# Dual_LPF_V1_2_Bottom.net
KiCad netlist of a schematic drawn in EAGLE
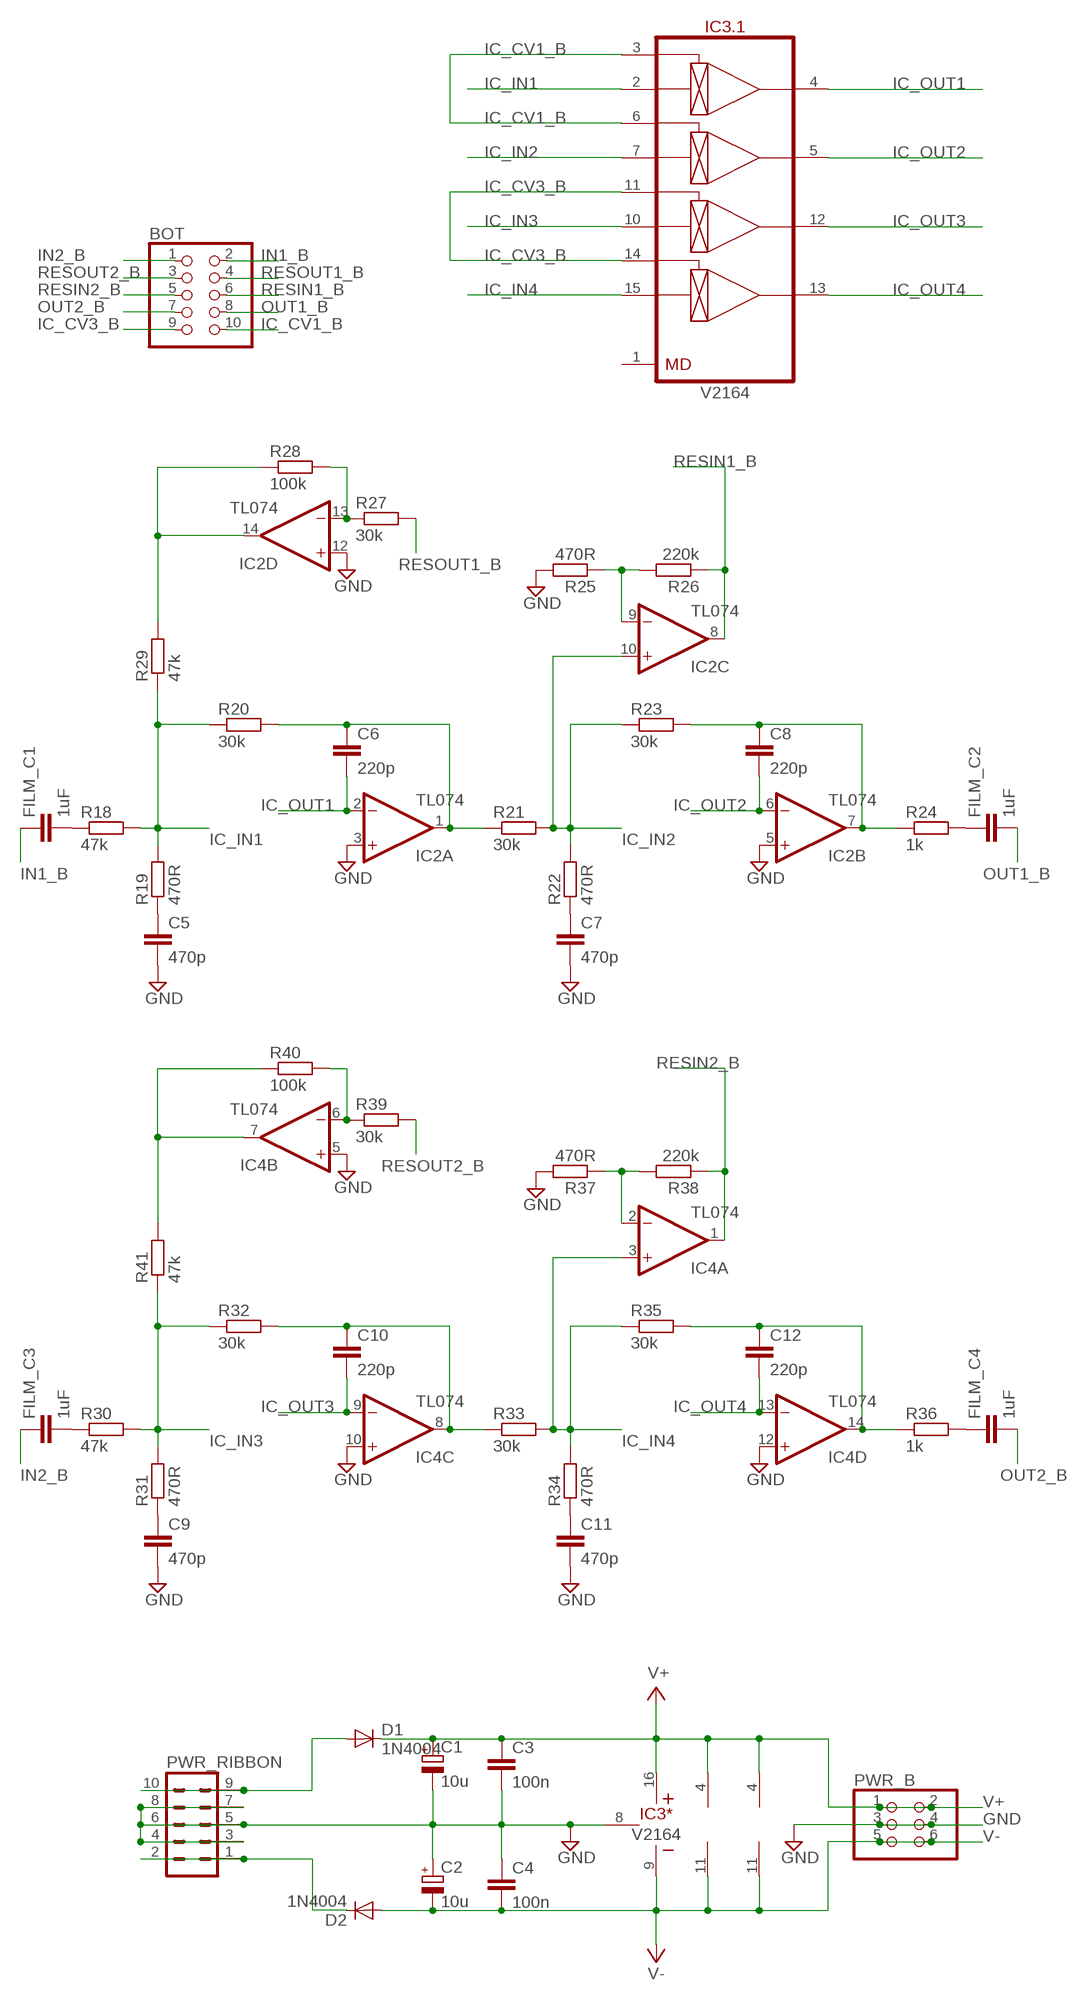
[diagram p0: schematic, sheet 1]

(export (version "E")
  (design (tool "Eeschema 10.0.6"))
  (components
    (comp (ref "BOT")
      (value "PINHD-2X5")
      (footprint "eagle-import:2X05")
      (libsource (lib "eagle-import") (part "PINHD-2X5"))
    )
    (comp (ref "C1")
      (value "10u")
      (footprint "eagle-import:E5-10,5")
      (libsource (lib "eagle-import") (part "CPOL-EUE5-10.5"))
    )
    (comp (ref "C2")
      (value "10u")
      (footprint "eagle-import:E5-10,5")
      (libsource (lib "eagle-import") (part "CPOL-EUE5-10.5"))
    )
    (comp (ref "C3")
      (value "100n")
      (footprint "eagle-import:C050-024X044")
      (libsource (lib "eagle-import") (part "C-EU050-024X044"))
    )
    (comp (ref "C4")
      (value "100n")
      (footprint "eagle-import:C050-024X044")
      (libsource (lib "eagle-import") (part "C-EU050-024X044"))
    )
    (comp (ref "C5")
      (value "470p")
      (footprint "eagle-import:C050-024X044")
      (libsource (lib "eagle-import") (part "C-EU050-024X044"))
    )
    (comp (ref "C6")
      (value "220p")
      (footprint "eagle-import:C050-024X044")
      (libsource (lib "eagle-import") (part "C-EU050-024X044"))
    )
    (comp (ref "C7")
      (value "470p")
      (footprint "eagle-import:C050-024X044")
      (libsource (lib "eagle-import") (part "C-EU050-024X044"))
    )
    (comp (ref "C8")
      (value "220p")
      (footprint "eagle-import:C050-024X044")
      (libsource (lib "eagle-import") (part "C-EU050-024X044"))
    )
    (comp (ref "C9")
      (value "470p")
      (footprint "eagle-import:C050-024X044")
      (libsource (lib "eagle-import") (part "C-EU050-024X044"))
    )
    (comp (ref "C10")
      (value "220p")
      (footprint "eagle-import:C050-024X044")
      (libsource (lib "eagle-import") (part "C-EU050-024X044"))
    )
    (comp (ref "C11")
      (value "470p")
      (footprint "eagle-import:C050-024X044")
      (libsource (lib "eagle-import") (part "C-EU050-024X044"))
    )
    (comp (ref "C12")
      (value "220p")
      (footprint "eagle-import:C050-024X044")
      (libsource (lib "eagle-import") (part "C-EU050-024X044"))
    )
    (comp (ref "D1")
      (value "1N4004")
      (footprint "eagle-import:DO41-10")
      (libsource (lib "eagle-import") (part "1N4004"))
    )
    (comp (ref "D2")
      (value "1N4004")
      (footprint "eagle-import:DO41-10")
      (libsource (lib "eagle-import") (part "1N4004"))
    )
    (comp (ref "FILM_C1")
      (value "1uF")
      (footprint "eagle-import:C050-045X075")
      (libsource (lib "eagle-import") (part "C-EU050-045X075"))
    )
    (comp (ref "FILM_C2")
      (value "1uF")
      (footprint "eagle-import:C050-045X075")
      (libsource (lib "eagle-import") (part "C-EU050-045X075"))
    )
    (comp (ref "FILM_C3")
      (value "1uF")
      (footprint "eagle-import:C050-045X075")
      (libsource (lib "eagle-import") (part "C-EU050-045X075"))
    )
    (comp (ref "FILM_C4")
      (value "1uF")
      (footprint "eagle-import:C050-045X075")
      (libsource (lib "eagle-import") (part "C-EU050-045X075"))
    )
    (comp (ref "IC2")
      (value "TL074")
      (footprint "eagle-import:DIL14")
      (libsource (lib "eagle-import") (part "TL074_"))
    )
    (comp (ref "IC3")
      (value "V2164")
      (footprint "eagle-import:DIP-16")
      (libsource (lib "eagle-import") (part "V2164D"))
    )
    (comp (ref "IC4")
      (value "TL074")
      (footprint "eagle-import:DIL14")
      (libsource (lib "eagle-import") (part "TL074_"))
    )
    (comp (ref "PWR_B")
      (value "PINHD-2X3")
      (footprint "eagle-import:2X03")
      (libsource (lib "eagle-import") (part "PINHD-2X3"))
    )
    (comp (ref "PWR_RIBBON")
      (value "EURO_POWER_HEADERFAT_PADS")
      (footprint "eagle-import:EURO_PWR_HEADER_FAT")
      (libsource (lib "eagle-import") (part "EURO_POWER_HEADERFAT_PADS"))
    )
    (comp (ref "R18")
      (value "47k")
      (footprint "eagle-import:0207_7")
      (libsource (lib "eagle-import") (part "R-EU_0207/7"))
    )
    (comp (ref "R19")
      (value "470R")
      (footprint "eagle-import:0207_7")
      (libsource (lib "eagle-import") (part "R-EU_0207/7"))
    )
    (comp (ref "R20")
      (value "30k")
      (footprint "eagle-import:0207_7")
      (libsource (lib "eagle-import") (part "R-EU_0207/7"))
    )
    (comp (ref "R21")
      (value "30k")
      (footprint "eagle-import:0207_7")
      (libsource (lib "eagle-import") (part "R-EU_0207/7"))
    )
    (comp (ref "R22")
      (value "470R")
      (footprint "eagle-import:0207_7")
      (libsource (lib "eagle-import") (part "R-EU_0207/7"))
    )
    (comp (ref "R23")
      (value "30k")
      (footprint "eagle-import:0207_7")
      (libsource (lib "eagle-import") (part "R-EU_0207/7"))
    )
    (comp (ref "R24")
      (value "1k")
      (footprint "eagle-import:0207_7")
      (libsource (lib "eagle-import") (part "R-EU_0207/7"))
    )
    (comp (ref "R25")
      (value "470R")
      (footprint "eagle-import:0207_7")
      (libsource (lib "eagle-import") (part "R-EU_0207/7"))
    )
    (comp (ref "R26")
      (value "220k")
      (footprint "eagle-import:0207_7")
      (libsource (lib "eagle-import") (part "R-EU_0207/7"))
    )
    (comp (ref "R27")
      (value "30k")
      (footprint "eagle-import:0207_7")
      (libsource (lib "eagle-import") (part "R-EU_0207/7"))
    )
    (comp (ref "R28")
      (value "100k")
      (footprint "eagle-import:0207_7")
      (libsource (lib "eagle-import") (part "R-EU_0207/7"))
    )
    (comp (ref "R29")
      (value "47k")
      (footprint "eagle-import:0207_7")
      (libsource (lib "eagle-import") (part "R-EU_0207/7"))
    )
    (comp (ref "R30")
      (value "47k")
      (footprint "eagle-import:0207_7")
      (libsource (lib "eagle-import") (part "R-EU_0207/7"))
    )
    (comp (ref "R31")
      (value "470R")
      (footprint "eagle-import:0207_7")
      (libsource (lib "eagle-import") (part "R-EU_0207/7"))
    )
    (comp (ref "R32")
      (value "30k")
      (footprint "eagle-import:0207_7")
      (libsource (lib "eagle-import") (part "R-EU_0207/7"))
    )
    (comp (ref "R33")
      (value "30k")
      (footprint "eagle-import:0207_7")
      (libsource (lib "eagle-import") (part "R-EU_0207/7"))
    )
    (comp (ref "R34")
      (value "470R")
      (footprint "eagle-import:0207_7")
      (libsource (lib "eagle-import") (part "R-EU_0207/7"))
    )
    (comp (ref "R35")
      (value "30k")
      (footprint "eagle-import:0207_7")
      (libsource (lib "eagle-import") (part "R-EU_0207/7"))
    )
    (comp (ref "R36")
      (value "1k")
      (footprint "eagle-import:0207_7")
      (libsource (lib "eagle-import") (part "R-EU_0207/7"))
    )
    (comp (ref "R37")
      (value "470R")
      (footprint "eagle-import:0207_7")
      (libsource (lib "eagle-import") (part "R-EU_0207/7"))
    )
    (comp (ref "R38")
      (value "220k")
      (footprint "eagle-import:0207_7")
      (libsource (lib "eagle-import") (part "R-EU_0207/7"))
    )
    (comp (ref "R39")
      (value "30k")
      (footprint "eagle-import:0207_7")
      (libsource (lib "eagle-import") (part "R-EU_0207/7"))
    )
    (comp (ref "R40")
      (value "100k")
      (footprint "eagle-import:0207_7")
      (libsource (lib "eagle-import") (part "R-EU_0207/7"))
    )
    (comp (ref "R41")
      (value "47k")
      (footprint "eagle-import:0207_7")
      (libsource (lib "eagle-import") (part "R-EU_0207/7"))
    )
  )
  (nets
    (net (code "1") (name "/IC_CV1_B") (class "Default")
      (node (ref "BOT") (pin "10") (pinfunction "10_10") (pintype "passive"))
      (node (ref "IC3") (pin "3") (pinfunction "CV1_3") (pintype "input"))
      (node (ref "IC3") (pin "6") (pinfunction "CV2_6") (pintype "input"))
    )
    (net (code "2") (name "/IC_CV3_B") (class "Default")
      (node (ref "BOT") (pin "9") (pinfunction "9_9") (pintype "passive"))
      (node (ref "IC3") (pin "11") (pinfunction "CV3_11") (pintype "input"))
      (node (ref "IC3") (pin "14") (pinfunction "CV4_14") (pintype "input"))
    )
    (net (code "3") (name "/IC_IN1") (class "Default")
      (node (ref "IC3") (pin "2") (pinfunction "IN1_2") (pintype "input"))
      (node (ref "R18") (pin "2") (pinfunction "2_2") (pintype "passive"))
      (node (ref "R19") (pin "2") (pinfunction "2_2") (pintype "passive"))
      (node (ref "R20") (pin "1") (pinfunction "1_1") (pintype "passive"))
      (node (ref "R29") (pin "1") (pinfunction "1_1") (pintype "passive"))
    )
    (net (code "4") (name "/IC_IN2") (class "Default")
      (node (ref "IC2") (pin "10") (pinfunction "+IN_10") (pintype "input"))
      (node (ref "IC3") (pin "7") (pinfunction "IN2_7") (pintype "input"))
      (node (ref "R21") (pin "2") (pinfunction "2_2") (pintype "passive"))
      (node (ref "R22") (pin "2") (pinfunction "2_2") (pintype "passive"))
      (node (ref "R23") (pin "1") (pinfunction "1_1") (pintype "passive"))
    )
    (net (code "5") (name "/IC_IN3") (class "Default")
      (node (ref "IC3") (pin "10") (pinfunction "IN3_10") (pintype "input"))
      (node (ref "R30") (pin "2") (pinfunction "2_2") (pintype "passive"))
      (node (ref "R31") (pin "2") (pinfunction "2_2") (pintype "passive"))
      (node (ref "R32") (pin "1") (pinfunction "1_1") (pintype "passive"))
      (node (ref "R41") (pin "1") (pinfunction "1_1") (pintype "passive"))
    )
    (net (code "6") (name "/IC_IN4") (class "Default")
      (node (ref "IC3") (pin "15") (pinfunction "IN4_15") (pintype "input"))
      (node (ref "IC4") (pin "3") (pinfunction "+IN_3") (pintype "input"))
      (node (ref "R33") (pin "2") (pinfunction "2_2") (pintype "passive"))
      (node (ref "R34") (pin "2") (pinfunction "2_2") (pintype "passive"))
      (node (ref "R35") (pin "1") (pinfunction "1_1") (pintype "passive"))
    )
    (net (code "7") (name "/IC_OUT1") (class "Default")
      (node (ref "C6") (pin "2") (pinfunction "2_2") (pintype "passive"))
      (node (ref "IC2") (pin "2") (pinfunction "-IN_2") (pintype "input"))
      (node (ref "IC3") (pin "4") (pinfunction "OUT1_4") (pintype "output"))
    )
    (net (code "8") (name "/IC_OUT2") (class "Default")
      (node (ref "C8") (pin "2") (pinfunction "2_2") (pintype "passive"))
      (node (ref "IC2") (pin "6") (pinfunction "-IN_6") (pintype "input"))
      (node (ref "IC3") (pin "5") (pinfunction "OUT2_5") (pintype "output"))
    )
    (net (code "9") (name "/IC_OUT3") (class "Default")
      (node (ref "C10") (pin "2") (pinfunction "2_2") (pintype "passive"))
      (node (ref "IC3") (pin "12") (pinfunction "OUT3_12") (pintype "output"))
      (node (ref "IC4") (pin "9") (pinfunction "-IN_9") (pintype "input"))
    )
    (net (code "10") (name "/IC_OUT4") (class "Default")
      (node (ref "C12") (pin "2") (pinfunction "2_2") (pintype "passive"))
      (node (ref "IC3") (pin "13") (pinfunction "OUT4_13") (pintype "output"))
      (node (ref "IC4") (pin "13") (pinfunction "-IN_13") (pintype "input"))
    )
    (net (code "11") (name "/IN1_B") (class "Default")
      (node (ref "BOT") (pin "2") (pinfunction "2_2") (pintype "passive"))
      (node (ref "FILM_C1") (pin "1") (pinfunction "1_1") (pintype "passive"))
    )
    (net (code "12") (name "/IN2_B") (class "Default")
      (node (ref "BOT") (pin "1") (pinfunction "1_1") (pintype "passive"))
      (node (ref "FILM_C3") (pin "1") (pinfunction "1_1") (pintype "passive"))
    )
    (net (code "13") (name "/OUT1_B") (class "Default")
      (node (ref "BOT") (pin "8") (pinfunction "8_8") (pintype "passive"))
      (node (ref "FILM_C2") (pin "2") (pinfunction "2_2") (pintype "passive"))
    )
    (net (code "14") (name "/OUT2_B") (class "Default")
      (node (ref "BOT") (pin "7") (pinfunction "7_7") (pintype "passive"))
      (node (ref "FILM_C4") (pin "2") (pinfunction "2_2") (pintype "passive"))
    )
    (net (code "15") (name "/RESIN1_B") (class "Default")
      (node (ref "BOT") (pin "6") (pinfunction "6_6") (pintype "passive"))
      (node (ref "IC2") (pin "8") (pinfunction "OUT_8") (pintype "output"))
      (node (ref "R26") (pin "1") (pinfunction "1_1") (pintype "passive"))
    )
    (net (code "16") (name "/RESIN2_B") (class "Default")
      (node (ref "BOT") (pin "5") (pinfunction "5_5") (pintype "passive"))
      (node (ref "IC4") (pin "1") (pinfunction "OUT_1") (pintype "output"))
      (node (ref "R38") (pin "1") (pinfunction "1_1") (pintype "passive"))
    )
    (net (code "17") (name "/RESOUT1_B") (class "Default")
      (node (ref "BOT") (pin "4") (pinfunction "4_4") (pintype "passive"))
      (node (ref "R27") (pin "2") (pinfunction "2_2") (pintype "passive"))
    )
    (net (code "18") (name "/RESOUT2_B") (class "Default")
      (node (ref "BOT") (pin "3") (pinfunction "3_3") (pintype "passive"))
      (node (ref "R39") (pin "2") (pinfunction "2_2") (pintype "passive"))
    )
    (net (code "19") (name "GND") (class "Default")
      (node (ref "C1") (pin "-") (pinfunction "-_-") (pintype "passive"))
      (node (ref "C11") (pin "2") (pinfunction "2_2") (pintype "passive"))
      (node (ref "C2") (pin "+") (pinfunction "+_+") (pintype "passive"))
      (node (ref "C3") (pin "2") (pinfunction "2_2") (pintype "passive"))
      (node (ref "C4") (pin "1") (pinfunction "1_1") (pintype "passive"))
      (node (ref "C5") (pin "2") (pinfunction "2_2") (pintype "passive"))
      (node (ref "C7") (pin "2") (pinfunction "2_2") (pintype "passive"))
      (node (ref "C9") (pin "2") (pinfunction "2_2") (pintype "passive"))
      (node (ref "IC2") (pin "12") (pinfunction "+IN_12") (pintype "input"))
      (node (ref "IC2") (pin "3") (pinfunction "+IN_3") (pintype "input"))
      (node (ref "IC2") (pin "5") (pinfunction "+IN_5") (pintype "input"))
      (node (ref "IC3") (pin "8") (pinfunction "GND_8") (pintype "power_in"))
      (node (ref "IC4") (pin "10") (pinfunction "+IN_10") (pintype "input"))
      (node (ref "IC4") (pin "12") (pinfunction "+IN_12") (pintype "input"))
      (node (ref "IC4") (pin "5") (pinfunction "+IN_5") (pintype "input"))
      (node (ref "PWR_B") (pin "3") (pinfunction "3_3") (pintype "passive"))
      (node (ref "PWR_B") (pin "4") (pinfunction "4_4") (pintype "passive"))
      (node (ref "PWR_RIBBON") (pin "3") (pinfunction "3_3") (pintype "passive"))
      (node (ref "PWR_RIBBON") (pin "4") (pinfunction "4_4") (pintype "passive"))
      (node (ref "PWR_RIBBON") (pin "5") (pinfunction "5_5") (pintype "passive"))
      (node (ref "PWR_RIBBON") (pin "6") (pinfunction "6_6") (pintype "passive"))
      (node (ref "PWR_RIBBON") (pin "7") (pinfunction "7_7") (pintype "passive"))
      (node (ref "PWR_RIBBON") (pin "8") (pinfunction "8_8") (pintype "passive"))
      (node (ref "R25") (pin "2") (pinfunction "2_2") (pintype "passive"))
      (node (ref "R37") (pin "2") (pinfunction "2_2") (pintype "passive"))
    )
    (net (code "20") (name "Net-(C5-Pad1)") (class "Default")
      (node (ref "C5") (pin "1") (pinfunction "1_1") (pintype "passive"))
      (node (ref "R19") (pin "1") (pinfunction "1_1") (pintype "passive"))
    )
    (net (code "21") (name "Net-(C7-Pad1)") (class "Default")
      (node (ref "C7") (pin "1") (pinfunction "1_1") (pintype "passive"))
      (node (ref "R22") (pin "1") (pinfunction "1_1") (pintype "passive"))
    )
    (net (code "22") (name "Net-(C9-Pad1)") (class "Default")
      (node (ref "C9") (pin "1") (pinfunction "1_1") (pintype "passive"))
      (node (ref "R31") (pin "1") (pinfunction "1_1") (pintype "passive"))
    )
    (net (code "23") (name "Net-(C11-Pad1)") (class "Default")
      (node (ref "C11") (pin "1") (pinfunction "1_1") (pintype "passive"))
      (node (ref "R34") (pin "1") (pinfunction "1_1") (pintype "passive"))
    )
    (net (code "24") (name "Net-(D1-PadA)") (class "Default")
      (node (ref "D1") (pin "A") (pinfunction "A_A") (pintype "passive"))
      (node (ref "PWR_RIBBON") (pin "10") (pinfunction "10_10") (pintype "passive"))
      (node (ref "PWR_RIBBON") (pin "9") (pinfunction "9_9") (pintype "passive"))
    )
    (net (code "25") (name "Net-(D2-PadC)") (class "Default")
      (node (ref "D2") (pin "C") (pinfunction "C_C") (pintype "passive"))
      (node (ref "PWR_RIBBON") (pin "1") (pinfunction "1_1") (pintype "passive"))
      (node (ref "PWR_RIBBON") (pin "2") (pinfunction "2_2") (pintype "passive"))
    )
    (net (code "26") (name "Net-(FILM_C1-Pad2)") (class "Default")
      (node (ref "FILM_C1") (pin "2") (pinfunction "2_2") (pintype "passive"))
      (node (ref "R18") (pin "1") (pinfunction "1_1") (pintype "passive"))
    )
    (net (code "27") (name "Net-(FILM_C2-Pad1)") (class "Default")
      (node (ref "FILM_C2") (pin "1") (pinfunction "1_1") (pintype "passive"))
      (node (ref "R24") (pin "2") (pinfunction "2_2") (pintype "passive"))
    )
    (net (code "28") (name "Net-(FILM_C3-Pad2)") (class "Default")
      (node (ref "FILM_C3") (pin "2") (pinfunction "2_2") (pintype "passive"))
      (node (ref "R30") (pin "1") (pinfunction "1_1") (pintype "passive"))
    )
    (net (code "29") (name "Net-(FILM_C4-Pad1)") (class "Default")
      (node (ref "FILM_C4") (pin "1") (pinfunction "1_1") (pintype "passive"))
      (node (ref "R36") (pin "2") (pinfunction "2_2") (pintype "passive"))
    )
    (net (code "30") (name "Net-(IC2A-OUT)") (class "Default")
      (node (ref "C6") (pin "1") (pinfunction "1_1") (pintype "passive"))
      (node (ref "IC2") (pin "1") (pinfunction "OUT_1") (pintype "output"))
      (node (ref "R20") (pin "2") (pinfunction "2_2") (pintype "passive"))
      (node (ref "R21") (pin "1") (pinfunction "1_1") (pintype "passive"))
    )
    (net (code "31") (name "Net-(IC2B-OUT)") (class "Default")
      (node (ref "C8") (pin "1") (pinfunction "1_1") (pintype "passive"))
      (node (ref "IC2") (pin "7") (pinfunction "OUT_7") (pintype "output"))
      (node (ref "R23") (pin "2") (pinfunction "2_2") (pintype "passive"))
      (node (ref "R24") (pin "1") (pinfunction "1_1") (pintype "passive"))
    )
    (net (code "32") (name "Net-(IC2C--IN)") (class "Default")
      (node (ref "IC2") (pin "9") (pinfunction "-IN_9") (pintype "input"))
      (node (ref "R25") (pin "1") (pinfunction "1_1") (pintype "passive"))
      (node (ref "R26") (pin "2") (pinfunction "2_2") (pintype "passive"))
    )
    (net (code "33") (name "Net-(IC2D--IN)") (class "Default")
      (node (ref "IC2") (pin "13") (pinfunction "-IN_13") (pintype "input"))
      (node (ref "R27") (pin "1") (pinfunction "1_1") (pintype "passive"))
      (node (ref "R28") (pin "2") (pinfunction "2_2") (pintype "passive"))
    )
    (net (code "34") (name "Net-(IC2D-OUT)") (class "Default")
      (node (ref "IC2") (pin "14") (pinfunction "OUT_14") (pintype "output"))
      (node (ref "R28") (pin "1") (pinfunction "1_1") (pintype "passive"))
      (node (ref "R29") (pin "2") (pinfunction "2_2") (pintype "passive"))
    )
    (net (code "35") (name "Net-(IC4A--IN)") (class "Default")
      (node (ref "IC4") (pin "2") (pinfunction "-IN_2") (pintype "input"))
      (node (ref "R37") (pin "1") (pinfunction "1_1") (pintype "passive"))
      (node (ref "R38") (pin "2") (pinfunction "2_2") (pintype "passive"))
    )
    (net (code "36") (name "Net-(IC4B--IN)") (class "Default")
      (node (ref "IC4") (pin "6") (pinfunction "-IN_6") (pintype "input"))
      (node (ref "R39") (pin "1") (pinfunction "1_1") (pintype "passive"))
      (node (ref "R40") (pin "2") (pinfunction "2_2") (pintype "passive"))
    )
    (net (code "37") (name "Net-(IC4B-OUT)") (class "Default")
      (node (ref "IC4") (pin "7") (pinfunction "OUT_7") (pintype "output"))
      (node (ref "R40") (pin "1") (pinfunction "1_1") (pintype "passive"))
      (node (ref "R41") (pin "2") (pinfunction "2_2") (pintype "passive"))
    )
    (net (code "38") (name "Net-(IC4C-OUT)") (class "Default")
      (node (ref "C10") (pin "1") (pinfunction "1_1") (pintype "passive"))
      (node (ref "IC4") (pin "8") (pinfunction "OUT_8") (pintype "output"))
      (node (ref "R32") (pin "2") (pinfunction "2_2") (pintype "passive"))
      (node (ref "R33") (pin "1") (pinfunction "1_1") (pintype "passive"))
    )
    (net (code "39") (name "Net-(IC4D-OUT)") (class "Default")
      (node (ref "C12") (pin "1") (pinfunction "1_1") (pintype "passive"))
      (node (ref "IC4") (pin "14") (pinfunction "OUT_14") (pintype "output"))
      (node (ref "R35") (pin "2") (pinfunction "2_2") (pintype "passive"))
      (node (ref "R36") (pin "1") (pinfunction "1_1") (pintype "passive"))
    )
    (net (code "40") (name "V+") (class "Default")
      (node (ref "C1") (pin "+") (pinfunction "+_+") (pintype "passive"))
      (node (ref "C3") (pin "1") (pinfunction "1_1") (pintype "passive"))
      (node (ref "D1") (pin "C") (pinfunction "C_C") (pintype "passive"))
      (node (ref "IC2") (pin "4") (pinfunction "V+_4") (pintype "power_in"))
      (node (ref "IC3") (pin "16") (pinfunction "V+_16") (pintype "power_in"))
      (node (ref "IC4") (pin "4") (pinfunction "V+_4") (pintype "power_in"))
      (node (ref "PWR_B") (pin "1") (pinfunction "1_1") (pintype "passive"))
      (node (ref "PWR_B") (pin "2") (pinfunction "2_2") (pintype "passive"))
    )
    (net (code "41") (name "V-") (class "Default")
      (node (ref "C2") (pin "-") (pinfunction "-_-") (pintype "passive"))
      (node (ref "C4") (pin "2") (pinfunction "2_2") (pintype "passive"))
      (node (ref "D2") (pin "A") (pinfunction "A_A") (pintype "passive"))
      (node (ref "IC2") (pin "11") (pinfunction "V-_11") (pintype "power_in"))
      (node (ref "IC3") (pin "9") (pinfunction "V-_9") (pintype "power_in"))
      (node (ref "IC4") (pin "11") (pinfunction "V-_11") (pintype "power_in"))
      (node (ref "PWR_B") (pin "5") (pinfunction "5_5") (pintype "passive"))
      (node (ref "PWR_B") (pin "6") (pinfunction "6_6") (pintype "passive"))
    )
    (net (code "42") (name "unconnected-(IC3B-MD-Pad1)") (class "Default")
      (node (ref "IC3") (pin "1") (pinfunction "MD_1") (pintype "output"))
    )
  )
)
